# biggity.net
KiCad netlist of a schematic drawn in EAGLE
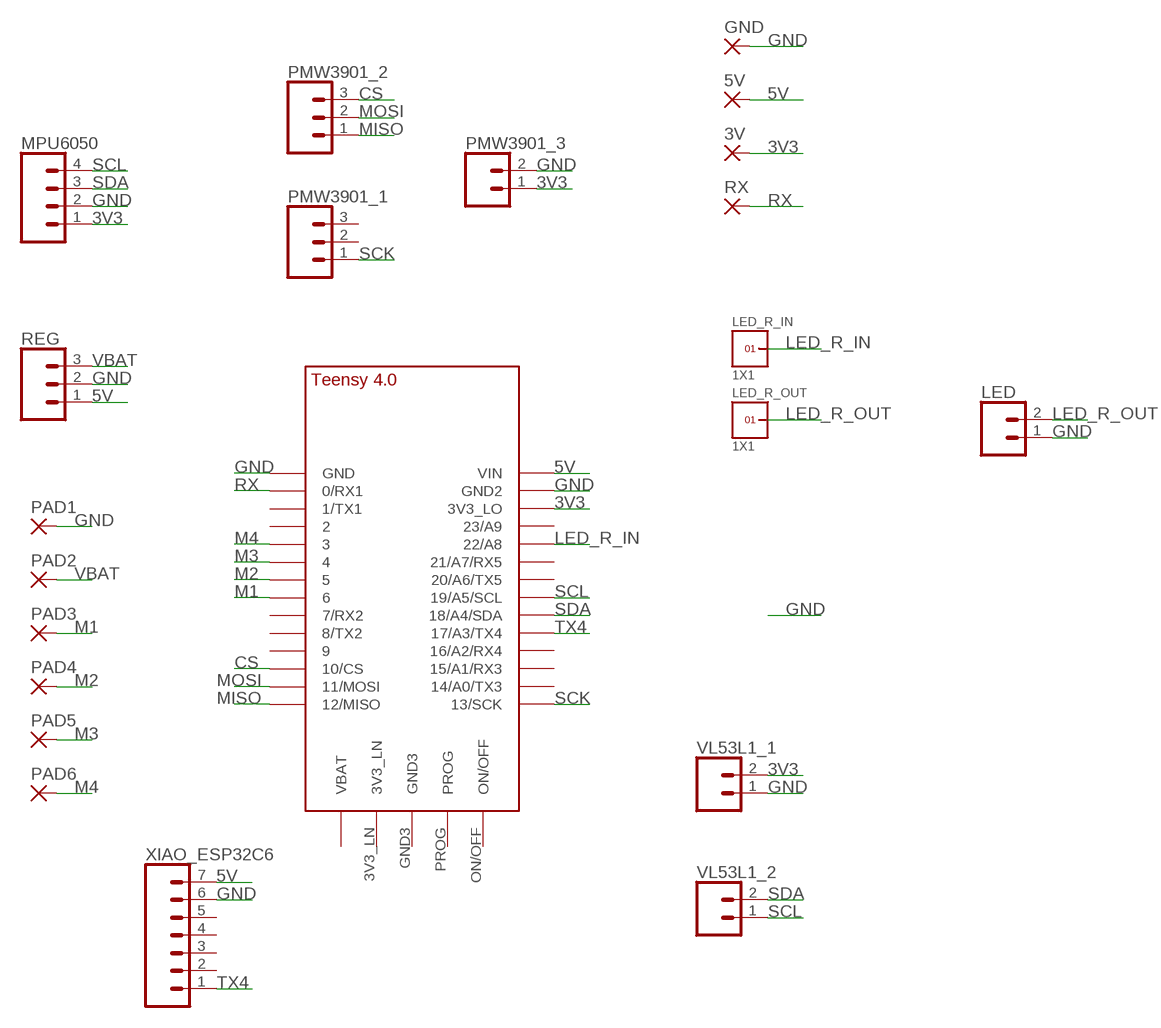
[diagram p0: schematic, sheet 1]

(export (version "E")
  (design (tool "Eeschema 10.0.6"))
  (components
    (comp (ref "3V")
      (value "SMD2")
      (footprint "eagle-import:SMD1,27-2,54")
      (libsource (lib "eagle-import") (part "SMD2"))
    )
    (comp (ref "5V")
      (value "SMD2")
      (footprint "eagle-import:SMD1,27-2,54")
      (libsource (lib "eagle-import") (part "SMD2"))
    )
    (comp (ref "GND")
      (value "SMD2")
      (footprint "eagle-import:SMD1,27-2,54")
      (libsource (lib "eagle-import") (part "SMD2"))
    )
    (comp (ref "LED")
      (value "CONN_021X02_NO_SILK")
      (footprint "eagle-import:1X02_NO_SILK")
      (libsource (lib "eagle-import") (part "CONN_021X02_NO_SILK"))
    )
    (comp (ref "LED_R_IN")
      (value "1X1")
      (footprint "eagle-import:1X1")
      (libsource (lib "eagle-import") (part "1X1"))
    )
    (comp (ref "LED_R_OUT")
      (value "1X1")
      (footprint "eagle-import:1X1")
      (libsource (lib "eagle-import") (part "1X1"))
    )
    (comp (ref "MPU6050")
      (value "CONN_041X04_NO_SILK")
      (footprint "eagle-import:1X04_NO_SILK")
      (libsource (lib "eagle-import") (part "CONN_041X04_NO_SILK"))
    )
    (comp (ref "PAD1")
      (value "SMD2")
      (footprint "eagle-import:SMD1,27-2,54")
      (libsource (lib "eagle-import") (part "SMD2"))
    )
    (comp (ref "PAD2")
      (value "SMD2")
      (footprint "eagle-import:SMD1,27-2,54")
      (libsource (lib "eagle-import") (part "SMD2"))
    )
    (comp (ref "PAD3")
      (value "SMD2")
      (footprint "eagle-import:SMD1,27-2,54")
      (libsource (lib "eagle-import") (part "SMD2"))
    )
    (comp (ref "PAD4")
      (value "SMD2")
      (footprint "eagle-import:SMD1,27-2,54")
      (libsource (lib "eagle-import") (part "SMD2"))
    )
    (comp (ref "PAD5")
      (value "SMD2")
      (footprint "eagle-import:SMD1,27-2,54")
      (libsource (lib "eagle-import") (part "SMD2"))
    )
    (comp (ref "PAD6")
      (value "SMD2")
      (footprint "eagle-import:SMD1,27-2,54")
      (libsource (lib "eagle-import") (part "SMD2"))
    )
    (comp (ref "PMW3901_1")
      (value "CONN_031X03_NO_SILK")
      (footprint "eagle-import:1X03_NO_SILK")
      (libsource (lib "eagle-import") (part "CONN_031X03_NO_SILK"))
    )
    (comp (ref "PMW3901_2")
      (value "CONN_031X03_NO_SILK")
      (footprint "eagle-import:1X03_NO_SILK")
      (libsource (lib "eagle-import") (part "CONN_031X03_NO_SILK"))
    )
    (comp (ref "PMW3901_3")
      (value "CONN_021X02_NO_SILK")
      (footprint "eagle-import:1X02_NO_SILK")
      (libsource (lib "eagle-import") (part "CONN_021X02_NO_SILK"))
    )
    (comp (ref "REG")
      (value "CONN_031X03_NO_SILK")
      (footprint "eagle-import:1X03_NO_SILK")
      (libsource (lib "eagle-import") (part "CONN_031X03_NO_SILK"))
    )
    (comp (ref "RX")
      (value "SMD2")
      (footprint "eagle-import:SMD1,27-2,54")
      (libsource (lib "eagle-import") (part "SMD2"))
    )
    (comp (ref "U$1")
      (value "TEENSY_4.0")
      (footprint "eagle-import:TEENSY_4.0")
      (libsource (lib "eagle-import") (part "TEENSY_4.0"))
    )
    (comp (ref "VL53L1_1")
      (value "CONN_021X02_NO_SILK")
      (footprint "eagle-import:1X02_NO_SILK")
      (libsource (lib "eagle-import") (part "CONN_021X02_NO_SILK"))
    )
    (comp (ref "VL53L1_2")
      (value "CONN_021X02_NO_SILK")
      (footprint "eagle-import:1X02_NO_SILK")
      (libsource (lib "eagle-import") (part "CONN_021X02_NO_SILK"))
    )
    (comp (ref "XIAO_ESP32C6")
      (value "CONN_07NO_SILK")
      (footprint "eagle-import:1X07_NO_SILK")
      (libsource (lib "eagle-import") (part "CONN_07NO_SILK"))
    )
  )
  (nets
    (net (code "1") (name "/3V3") (class "Default")
      (node (ref "3V") (pin "1") (pinfunction "P_1") (pintype "passive"))
      (node (ref "MPU6050") (pin "1") (pinfunction "1_1") (pintype "passive"))
      (node (ref "PMW3901_3") (pin "1") (pinfunction "1_1") (pintype "passive"))
      (node (ref "U$1") (pin "3V3_LO") (pinfunction "3V3_LO_3V3_LO") (pintype "bidirectional"))
      (node (ref "VL53L1_1") (pin "2") (pinfunction "2_2") (pintype "passive"))
    )
    (net (code "2") (name "/5V") (class "Default")
      (node (ref "5V") (pin "1") (pinfunction "P_1") (pintype "passive"))
      (node (ref "REG") (pin "1") (pinfunction "1_1") (pintype "passive"))
      (node (ref "U$1") (pin "VIN") (pinfunction "VIN_VIN") (pintype "bidirectional"))
      (node (ref "XIAO_ESP32C6") (pin "7") (pinfunction "7_7") (pintype "passive"))
    )
    (net (code "3") (name "/CS") (class "Default")
      (node (ref "PMW3901_2") (pin "3") (pinfunction "3_3") (pintype "passive"))
      (node (ref "U$1") (pin "10/CS") (pinfunction "10/CS_10/CS") (pintype "bidirectional"))
    )
    (net (code "4") (name "/GND") (class "Default")
      (node (ref "GND") (pin "1") (pinfunction "P_1") (pintype "passive"))
      (node (ref "LED") (pin "1") (pinfunction "1_1") (pintype "passive"))
      (node (ref "MPU6050") (pin "2") (pinfunction "2_2") (pintype "passive"))
      (node (ref "PAD1") (pin "1") (pinfunction "P_1") (pintype "passive"))
      (node (ref "PMW3901_3") (pin "2") (pinfunction "2_2") (pintype "passive"))
      (node (ref "REG") (pin "2") (pinfunction "2_2") (pintype "passive"))
      (node (ref "U$1") (pin "GND") (pinfunction "GND_GND") (pintype "bidirectional"))
      (node (ref "U$1") (pin "GND2") (pinfunction "GND2_GND2") (pintype "bidirectional"))
      (node (ref "VL53L1_1") (pin "1") (pinfunction "1_1") (pintype "passive"))
      (node (ref "XIAO_ESP32C6") (pin "6") (pinfunction "6_6") (pintype "passive"))
    )
    (net (code "5") (name "/LED_R_IN") (class "Default")
      (node (ref "LED_R_IN") (pin "1") (pinfunction "1_1") (pintype "bidirectional"))
      (node (ref "U$1") (pin "22/A8") (pinfunction "22/A8_22/A8") (pintype "bidirectional"))
    )
    (net (code "6") (name "/LED_R_OUT") (class "Default")
      (node (ref "LED") (pin "2") (pinfunction "2_2") (pintype "passive"))
      (node (ref "LED_R_OUT") (pin "1") (pinfunction "1_1") (pintype "bidirectional"))
    )
    (net (code "7") (name "/M1") (class "Default")
      (node (ref "PAD3") (pin "1") (pinfunction "P_1") (pintype "passive"))
      (node (ref "U$1") (pin "6") (pinfunction "6_6") (pintype "bidirectional"))
    )
    (net (code "8") (name "/M2") (class "Default")
      (node (ref "PAD4") (pin "1") (pinfunction "P_1") (pintype "passive"))
      (node (ref "U$1") (pin "5") (pinfunction "5_5") (pintype "bidirectional"))
    )
    (net (code "9") (name "/M3") (class "Default")
      (node (ref "PAD5") (pin "1") (pinfunction "P_1") (pintype "passive"))
      (node (ref "U$1") (pin "4/CANRX") (pinfunction "4_4/CANRX") (pintype "bidirectional"))
    )
    (net (code "10") (name "/M4") (class "Default")
      (node (ref "PAD6") (pin "1") (pinfunction "P_1") (pintype "passive"))
      (node (ref "U$1") (pin "3/CANTX") (pinfunction "3_3/CANTX") (pintype "bidirectional"))
    )
    (net (code "11") (name "/MISO") (class "Default")
      (node (ref "PMW3901_2") (pin "1") (pinfunction "1_1") (pintype "passive"))
      (node (ref "U$1") (pin "12/MISO") (pinfunction "12/MISO_12/MISO") (pintype "bidirectional"))
    )
    (net (code "12") (name "/MOSI") (class "Default")
      (node (ref "PMW3901_2") (pin "2") (pinfunction "2_2") (pintype "passive"))
      (node (ref "U$1") (pin "11/MOSI") (pinfunction "11/MOSI_11/MOSI") (pintype "bidirectional"))
    )
    (net (code "13") (name "/RX") (class "Default")
      (node (ref "RX") (pin "1") (pinfunction "P_1") (pintype "passive"))
      (node (ref "U$1") (pin "0/RX") (pinfunction "0/RX1_0/RX") (pintype "bidirectional"))
    )
    (net (code "14") (name "/SCK") (class "Default")
      (node (ref "PMW3901_1") (pin "1") (pinfunction "1_1") (pintype "passive"))
      (node (ref "U$1") (pin "13/SCK") (pinfunction "13/SCK_13/SCK") (pintype "bidirectional"))
    )
    (net (code "15") (name "/SCL") (class "Default")
      (node (ref "MPU6050") (pin "4") (pinfunction "4_4") (pintype "passive"))
      (node (ref "U$1") (pin "19/A5/SCL") (pinfunction "19/A5/SCL_19/A5/SCL") (pintype "bidirectional"))
      (node (ref "VL53L1_2") (pin "1") (pinfunction "1_1") (pintype "passive"))
    )
    (net (code "16") (name "/SDA") (class "Default")
      (node (ref "MPU6050") (pin "3") (pinfunction "3_3") (pintype "passive"))
      (node (ref "U$1") (pin "18/A4/SDA") (pinfunction "18/A4/SDA_18/A4/SDA") (pintype "bidirectional"))
      (node (ref "VL53L1_2") (pin "2") (pinfunction "2_2") (pintype "passive"))
    )
    (net (code "17") (name "/TX4") (class "Default")
      (node (ref "U$1") (pin "17/A3") (pinfunction "17/A3/TX4_17/A3") (pintype "bidirectional"))
      (node (ref "XIAO_ESP32C6") (pin "1") (pinfunction "1_1") (pintype "passive"))
    )
    (net (code "18") (name "/VBAT") (class "Default")
      (node (ref "PAD2") (pin "1") (pinfunction "P_1") (pintype "passive"))
      (node (ref "REG") (pin "3") (pinfunction "3_3") (pintype "passive"))
    )
    (net (code "19") (name "unconnected-(PMW3901_1-Pad2)") (class "Default")
      (node (ref "PMW3901_1") (pin "2") (pinfunction "2_2") (pintype "passive"))
    )
    (net (code "20") (name "unconnected-(PMW3901_1-Pad3)") (class "Default")
      (node (ref "PMW3901_1") (pin "3") (pinfunction "3_3") (pintype "passive"))
    )
    (net (code "21") (name "unconnected-(U$1-1{slash}TX1-Pad1{slash}TX)") (class "Default")
      (node (ref "U$1") (pin "1/TX") (pinfunction "1/TX1_1/TX") (pintype "bidirectional"))
    )
    (net (code "22") (name "unconnected-(U$1-7{slash}RX2-Pad7)") (class "Default")
      (node (ref "U$1") (pin "7") (pinfunction "7/RX2_7") (pintype "bidirectional"))
    )
    (net (code "23") (name "unconnected-(U$1-8{slash}TX2-Pad8)") (class "Default")
      (node (ref "U$1") (pin "8") (pinfunction "8/TX2_8") (pintype "bidirectional"))
    )
    (net (code "24") (name "unconnected-(U$1-9-Pad9{slash}CS)") (class "Default")
      (node (ref "U$1") (pin "9/CS") (pinfunction "9_9/CS") (pintype "bidirectional"))
    )
    (net (code "25") (name "unconnected-(U$1-14{slash}A0{slash}TX3-Pad14{slash}A0)") (class "Default")
      (node (ref "U$1") (pin "14/A0") (pinfunction "14/A0/TX3_14/A0") (pintype "bidirectional"))
    )
    (net (code "26") (name "unconnected-(U$1-15{slash}A1{slash}RX3-Pad15{slash}A1)") (class "Default")
      (node (ref "U$1") (pin "15/A1") (pinfunction "15/A1/RX3_15/A1") (pintype "bidirectional"))
    )
    (net (code "27") (name "unconnected-(U$1-16{slash}A2{slash}RX4-Pad16{slash}A2)") (class "Default")
      (node (ref "U$1") (pin "16/A2") (pinfunction "16/A2/RX4_16/A2") (pintype "bidirectional"))
    )
    (net (code "28") (name "unconnected-(U$1-20{slash}A6{slash}TX5-Pad20{slash}A6)") (class "Default")
      (node (ref "U$1") (pin "20/A6") (pinfunction "20/A6/TX5_20/A6") (pintype "bidirectional"))
    )
    (net (code "29") (name "unconnected-(U$1-21{slash}A7{slash}RX5-Pad21{slash}A7)") (class "Default")
      (node (ref "U$1") (pin "21/A7") (pinfunction "21/A7/RX5_21/A7") (pintype "bidirectional"))
    )
    (net (code "30") (name "unconnected-(U$1-Pad2)") (class "Default")
      (node (ref "U$1") (pin "2") (pinfunction "2_2") (pintype "bidirectional"))
    )
    (net (code "31") (name "unconnected-(U$1-Pad3V3_LN)") (class "Default")
      (node (ref "U$1") (pin "3V3_LN") (pinfunction "3V3_LN_3V3_LN") (pintype "bidirectional"))
    )
    (net (code "32") (name "unconnected-(U$1-Pad23{slash}A9)") (class "Default")
      (node (ref "U$1") (pin "23/A9") (pinfunction "23/A9_23/A9") (pintype "bidirectional"))
    )
    (net (code "33") (name "unconnected-(U$1-PadGND3)") (class "Default")
      (node (ref "U$1") (pin "GND3") (pinfunction "GND3_GND3") (pintype "bidirectional"))
    )
    (net (code "34") (name "unconnected-(U$1-PadON{slash}OFF)") (class "Default")
      (node (ref "U$1") (pin "ON/OFF") (pinfunction "ON/OFF_ON/OFF") (pintype "bidirectional"))
    )
    (net (code "35") (name "unconnected-(U$1-PadPROG)") (class "Default")
      (node (ref "U$1") (pin "PROG") (pinfunction "PROG_PROG") (pintype "bidirectional"))
    )
    (net (code "36") (name "unconnected-(U$1-VBAT-PadVBAT\\)") (class "Default")
      (node (ref "U$1") (pin "VBAT\\") (pinfunction "VBAT_VBAT\\") (pintype "bidirectional"))
    )
    (net (code "37") (name "unconnected-(XIAO_ESP32C6-Pad2)") (class "Default")
      (node (ref "XIAO_ESP32C6") (pin "2") (pinfunction "2_2") (pintype "passive"))
    )
    (net (code "38") (name "unconnected-(XIAO_ESP32C6-Pad3)") (class "Default")
      (node (ref "XIAO_ESP32C6") (pin "3") (pinfunction "3_3") (pintype "passive"))
    )
    (net (code "39") (name "unconnected-(XIAO_ESP32C6-Pad4)") (class "Default")
      (node (ref "XIAO_ESP32C6") (pin "4") (pinfunction "4_4") (pintype "passive"))
    )
    (net (code "40") (name "unconnected-(XIAO_ESP32C6-Pad5)") (class "Default")
      (node (ref "XIAO_ESP32C6") (pin "5") (pinfunction "5_5") (pintype "passive"))
    )
  )
)
